# AD8620.net
KiCad netlist of a schematic drawn in EAGLE
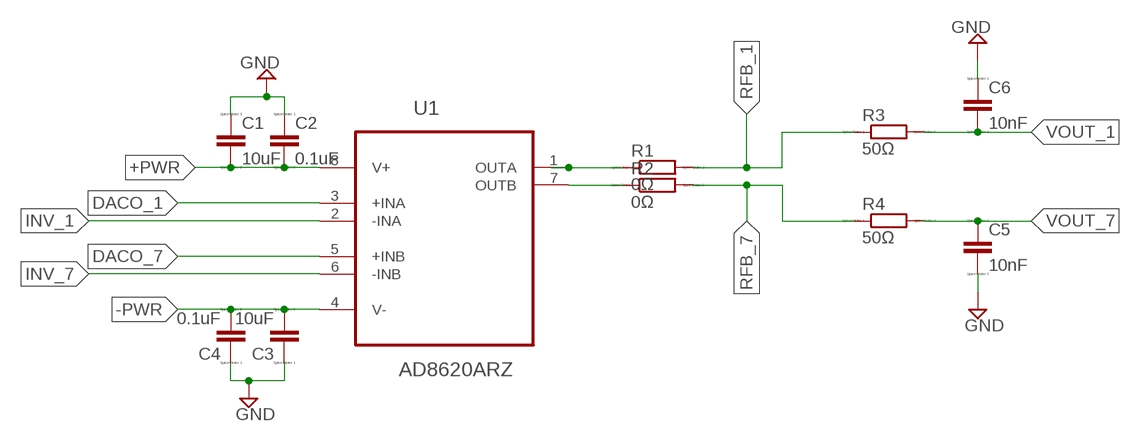
[diagram p0: schematic, sheet 1]

(export (version "E")
  (design (tool "Eeschema 10.0.6"))
  (components
    (comp (ref "C1")
      (value "10uF")
      (footprint "eagle-import:C0805")
      (libsource (lib "eagle-import") (part "C"))
    )
    (comp (ref "C2")
      (value "0.1uF")
      (footprint "eagle-import:C0603")
      (libsource (lib "eagle-import") (part "CC0603"))
    )
    (comp (ref "C3")
      (value "10uF")
      (footprint "eagle-import:C0805")
      (libsource (lib "eagle-import") (part "C"))
    )
    (comp (ref "C4")
      (value "0.1uF")
      (footprint "eagle-import:C0603")
      (libsource (lib "eagle-import") (part "CC0603"))
    )
    (comp (ref "C5")
      (value "10nF")
      (footprint "eagle-import:C0603")
      (libsource (lib "eagle-import") (part "CC0603"))
    )
    (comp (ref "C6")
      (value "10nF")
      (footprint "eagle-import:C0603")
      (libsource (lib "eagle-import") (part "CC0603"))
    )
    (comp (ref "R1")
      (value "0Ω")
      (footprint "eagle-import:R0603")
      (libsource (lib "eagle-import") (part "RR0603"))
    )
    (comp (ref "R2")
      (value "0Ω")
      (footprint "eagle-import:R0603")
      (libsource (lib "eagle-import") (part "RR0603"))
    )
    (comp (ref "R3")
      (value "50Ω")
      (footprint "eagle-import:R0603")
      (libsource (lib "eagle-import") (part "RR0603"))
    )
    (comp (ref "R4")
      (value "50Ω")
      (footprint "eagle-import:R0603")
      (libsource (lib "eagle-import") (part "RR0603"))
    )
    (comp (ref "U1")
      (value "AD8620ARZ")
      (footprint "eagle-import:SOIC127P600X175-8N")
      (libsource (lib "eagle-import") (part "AD8620ARZ"))
    )
  )
  (nets
    (net (code "1") (name "+PWR") (class "Default")
      (node (ref "C1") (pin "2") (pinfunction "2_2") (pintype "passive"))
      (node (ref "C2") (pin "2") (pinfunction "2_2") (pintype "passive"))
      (node (ref "U1") (pin "8") (pinfunction "V+_8") (pintype "power_in"))
    )
    (net (code "2") (name "-PWR") (class "Default")
      (node (ref "C3") (pin "2") (pinfunction "2_2") (pintype "passive"))
      (node (ref "C4") (pin "2") (pinfunction "2_2") (pintype "passive"))
      (node (ref "U1") (pin "4") (pinfunction "V-_4") (pintype "power_in"))
    )
    (net (code "3") (name "DACO_1") (class "Default")
      (node (ref "U1") (pin "3") (pinfunction "+INA_3") (pintype "input"))
    )
    (net (code "4") (name "DACO_7") (class "Default")
      (node (ref "U1") (pin "5") (pinfunction "+INB_5") (pintype "input"))
    )
    (net (code "5") (name "GND") (class "Default")
      (node (ref "C1") (pin "1") (pinfunction "1_1") (pintype "passive"))
      (node (ref "C2") (pin "1") (pinfunction "1_1") (pintype "passive"))
      (node (ref "C3") (pin "1") (pinfunction "1_1") (pintype "passive"))
      (node (ref "C4") (pin "1") (pinfunction "1_1") (pintype "passive"))
      (node (ref "C5") (pin "2") (pinfunction "2_2") (pintype "passive"))
      (node (ref "C6") (pin "1") (pinfunction "1_1") (pintype "passive"))
    )
    (net (code "6") (name "INV_1") (class "Default")
      (node (ref "U1") (pin "2") (pinfunction "-INA_2") (pintype "input"))
    )
    (net (code "7") (name "INV_7") (class "Default")
      (node (ref "U1") (pin "6") (pinfunction "-INB_6") (pintype "input"))
    )
    (net (code "8") (name "Net-(U1-OUTA)") (class "Default")
      (node (ref "R1") (pin "1") (pinfunction "1_1") (pintype "passive"))
      (node (ref "U1") (pin "1") (pinfunction "OUTA_1") (pintype "output"))
    )
    (net (code "9") (name "Net-(U1-OUTB)") (class "Default")
      (node (ref "R2") (pin "1") (pinfunction "1_1") (pintype "passive"))
      (node (ref "U1") (pin "7") (pinfunction "OUTB_7") (pintype "output"))
    )
    (net (code "10") (name "RFB_1") (class "Default")
      (node (ref "R1") (pin "2") (pinfunction "2_2") (pintype "passive"))
      (node (ref "R3") (pin "1") (pinfunction "1_1") (pintype "passive"))
    )
    (net (code "11") (name "RFB_7") (class "Default")
      (node (ref "R2") (pin "2") (pinfunction "2_2") (pintype "passive"))
      (node (ref "R4") (pin "1") (pinfunction "1_1") (pintype "passive"))
    )
    (net (code "12") (name "VOUT_1") (class "Default")
      (node (ref "C6") (pin "2") (pinfunction "2_2") (pintype "passive"))
      (node (ref "R3") (pin "2") (pinfunction "2_2") (pintype "passive"))
    )
    (net (code "13") (name "VOUT_7") (class "Default")
      (node (ref "C5") (pin "1") (pinfunction "1_1") (pintype "passive"))
      (node (ref "R4") (pin "2") (pinfunction "2_2") (pintype "passive"))
    )
  )
)
